# 1117_3_3V_SMD_0603.net
KiCad netlist of a schematic drawn in EAGLE
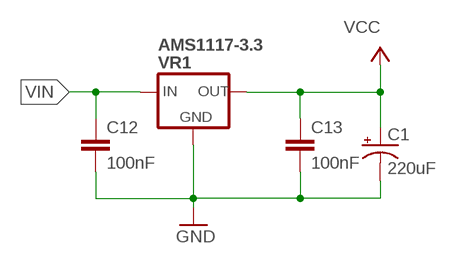
[diagram p0: schematic, sheet 1]

(export (version "E")
  (design (tool "Eeschema 10.0.6"))
  (components
    (comp (ref "C1")
      (value "220uF")
      (footprint "eagle-import:UD-6,3X7,7_NICHICON")
      (libsource (lib "eagle-import") (part "CPOL-USUD-6,3X7,7"))
    )
    (comp (ref "C12")
      (value "100nF")
      (footprint "eagle-import:C0603")
      (libsource (lib "eagle-import") (part "C-EUC0603"))
    )
    (comp (ref "C13")
      (value "100nF")
      (footprint "eagle-import:C0603")
      (libsource (lib "eagle-import") (part "C-EUC0603"))
    )
    (comp (ref "VR1")
      (value "AMS1117-3.3")
      (footprint "eagle-import:SOT223")
      (libsource (lib "eagle-import") (part "NCP1117ST50T3G"))
    )
  )
  (nets
    (net (code "1") (name "GND") (class "Default")
      (node (ref "C1") (pin "-") (pinfunction "-_-") (pintype "passive"))
      (node (ref "C12") (pin "2") (pinfunction "2_2") (pintype "passive"))
      (node (ref "C13") (pin "2") (pinfunction "2_2") (pintype "passive"))
      (node (ref "VR1") (pin "1") (pinfunction "GND_1") (pintype "input"))
    )
    (net (code "2") (name "VCC") (class "Default")
      (node (ref "C1") (pin "+") (pinfunction "+_+") (pintype "passive"))
      (node (ref "C13") (pin "1") (pinfunction "1_1") (pintype "passive"))
      (node (ref "VR1") (pin "2") (pinfunction "OUT_2") (pintype "output"))
      (node (ref "VR1") (pin "4") (pinfunction "OUT_4") (pintype "output"))
    )
    (net (code "3") (name "VIN") (class "Default")
      (node (ref "C12") (pin "1") (pinfunction "1_1") (pintype "passive"))
      (node (ref "VR1") (pin "3") (pinfunction "IN_3") (pintype "input"))
    )
  )
)
